# npm1300_qeaa_config4.net
KiCad netlist of a schematic drawn in Altium Designer
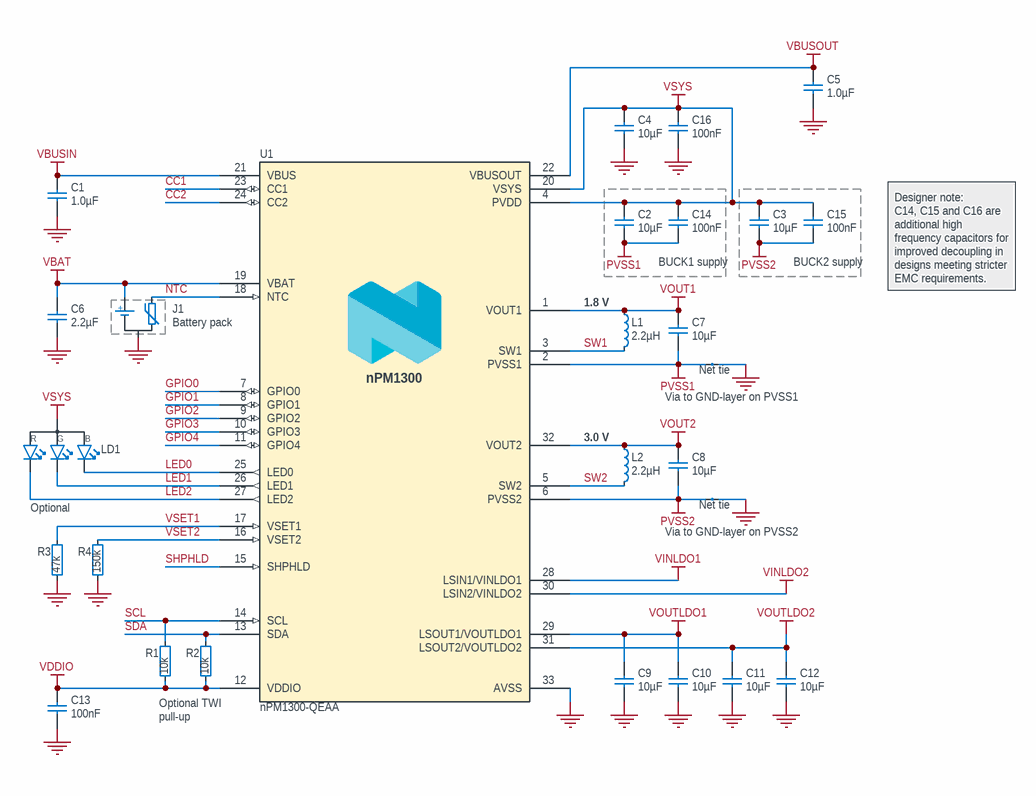
[diagram p0: npm1300_qeaa_config4.SchDoc]

(export (version "E")
  (design (tool "Eeschema 10.0.6"))
  (components
    (comp (ref "C1")
      (value "1.0µF")
      (footprint "CAPC1608X06L")
      (description "Capacitor, Ceramic, 1.0µF 10V X5R 0603,±10%")
      (fields
        (field (name "PART NUMBER") "C0603-1µ0-10V-X5R")
        (field (name "MANUFACTURER") "N.A.")
        (field (name "AUTHOR") "getr")
      )
      (libsource (lib "AltiumLib") (part "CAP"))
    )
    (comp (ref "C2")
      (value "10µF")
      (footprint "CAPC1608X06L")
      (description "Capacitor, X5R, ±20%")
      (fields
        (field (name "PART NUMBER") "C0603-10µ")
        (field (name "MANUFACTURER") "N.A.")
        (field (name "AUTHOR") "rsk")
      )
      (libsource (lib "AltiumLib") (part "CAP"))
    )
    (comp (ref "C3")
      (value "10µF")
      (footprint "CAPC1608X06L")
      (description "Capacitor, X5R, ±20%")
      (fields
        (field (name "PART NUMBER") "C0603-10µ")
        (field (name "MANUFACTURER") "N.A.")
        (field (name "AUTHOR") "rsk")
      )
      (libsource (lib "AltiumLib") (part "CAP"))
    )
    (comp (ref "C4")
      (value "10µF")
      (footprint "CAPC1608X06L")
      (description "Capacitor, X5R, ±20%")
      (fields
        (field (name "PART NUMBER") "C0603-10µ")
        (field (name "MANUFACTURER") "N.A.")
        (field (name "AUTHOR") "rsk")
      )
      (libsource (lib "AltiumLib") (part "CAP"))
    )
    (comp (ref "C5")
      (value "1.0µF")
      (footprint "CAPC1608X06L")
      (description "Capacitor, Ceramic, 1.0µF 10V X5R 0603,±10%")
      (fields
        (field (name "PART NUMBER") "C0603-1µ0-10V-X5R")
        (field (name "MANUFACTURER") "N.A.")
        (field (name "AUTHOR") "getr")
      )
      (libsource (lib "AltiumLib") (part "CAP"))
    )
    (comp (ref "C6")
      (value "2.2µF")
      (footprint "CAPC1608X06L")
      (description "Capacitor, Ceramic, X7R, ±10%, 16V")
      (fields
        (field (name "PART NUMBER") "C0603-2.2µ-16V-X7R")
        (field (name "MANUFACTURER") "Taiyo Yuden")
        (field (name "AUTHOR") "rsk")
      )
      (libsource (lib "AltiumLib") (part "CAP"))
    )
    (comp (ref "C7")
      (value "10µF")
      (footprint "CAPC1608X06L")
      (description "Capacitor, X5R, ±20%")
      (fields
        (field (name "PART NUMBER") "C0603-10µ")
        (field (name "MANUFACTURER") "N.A.")
        (field (name "AUTHOR") "rsk")
      )
      (libsource (lib "AltiumLib") (part "CAP"))
    )
    (comp (ref "C8")
      (value "10µF")
      (footprint "CAPC1608X06L")
      (description "Capacitor, X5R, ±20%")
      (fields
        (field (name "PART NUMBER") "C0603-10µ")
        (field (name "MANUFACTURER") "N.A.")
        (field (name "AUTHOR") "rsk")
      )
      (libsource (lib "AltiumLib") (part "CAP"))
    )
    (comp (ref "C9")
      (value "10µF")
      (footprint "CAPC1608X06L")
      (description "Capacitor, X5R, ±20%")
      (fields
        (field (name "PART NUMBER") "C0603-10µ")
        (field (name "MANUFACTURER") "N.A.")
        (field (name "AUTHOR") "rsk")
      )
      (libsource (lib "AltiumLib") (part "CAP"))
    )
    (comp (ref "C10")
      (value "10µF")
      (footprint "CAPC1608X06L")
      (description "Capacitor, X5R, ±20%")
      (fields
        (field (name "PART NUMBER") "C0603-10µ")
        (field (name "MANUFACTURER") "N.A.")
        (field (name "AUTHOR") "rsk")
      )
      (libsource (lib "AltiumLib") (part "CAP"))
    )
    (comp (ref "C11")
      (value "10µF")
      (footprint "CAPC1608X06L")
      (description "Capacitor, X5R, ±20%")
      (fields
        (field (name "PART NUMBER") "C0603-10µ")
        (field (name "MANUFACTURER") "N.A.")
        (field (name "AUTHOR") "rsk")
      )
      (libsource (lib "AltiumLib") (part "CAP"))
    )
    (comp (ref "C12")
      (value "10µF")
      (footprint "CAPC1608X06L")
      (description "Capacitor, X5R, ±20%")
      (fields
        (field (name "PART NUMBER") "C0603-10µ")
        (field (name "MANUFACTURER") "N.A.")
        (field (name "AUTHOR") "rsk")
      )
      (libsource (lib "AltiumLib") (part "CAP"))
    )
    (comp (ref "C13")
      (value "100nF")
      (footprint "CAPC0603X03L_C")
      (description "Capacitor, X5R, ±10%, 100nF, 16V")
      (fields
        (field (name "PART NUMBER") "C0201-100n")
        (field (name "MANUFACTURER") "N.A.")
        (field (name "AUTHOR") "rsk")
      )
      (libsource (lib "AltiumLib") (part "CAP"))
    )
    (comp (ref "C14")
      (value "100nF")
      (footprint "CAPC1005X04L")
      (description "Capacitor, Ceramic, X7R, ±20%, 16V")
      (fields
        (field (name "PART NUMBER") "C0402-100n-16V-X7R-C0402C104M4RAC7867")
        (field (name "MANUFACTURER") "Kemet")
        (field (name "AUTHOR") "getr")
      )
      (libsource (lib "AltiumLib") (part "CAP"))
    )
    (comp (ref "C15")
      (value "100nF")
      (footprint "CAPC1005X04L")
      (description "Capacitor, Ceramic, X7R, ±20%, 16V")
      (fields
        (field (name "PART NUMBER") "C0402-100n-16V-X7R-C0402C104M4RAC7867")
        (field (name "MANUFACTURER") "Kemet")
        (field (name "AUTHOR") "getr")
      )
      (libsource (lib "AltiumLib") (part "CAP"))
    )
    (comp (ref "C16")
      (value "100nF")
      (footprint "CAPC1005X04L")
      (description "Capacitor, Ceramic, X7R, ±20%, 16V")
      (fields
        (field (name "PART NUMBER") "C0402-100n-16V-X7R-C0402C104M4RAC7867")
        (field (name "MANUFACTURER") "Kemet")
        (field (name "AUTHOR") "getr")
      )
      (libsource (lib "AltiumLib") (part "CAP"))
    )
    (comp (ref "J1")
      (value "Battery pack")
      (footprint "TP_3x1mm_TH")
      (description "Battery pack with NTC")
      (fields
        (field (name "PART NUMBER") "Battery_w/NTC_TP")
        (field (name "MANUFACTURER") "N.A.")
        (field (name "AUTHOR") "rsk")
      )
      (libsource (lib "AltiumLib") (part "Battery_pack_NTC"))
    )
    (comp (ref "L1")
      (value "2.2µH")
      (footprint "INDC2016X10N")
      (description "Inductor, Irms=2.5A, Isat=2.9A, ±20%, DCR=73mΩ")
      (fields
        (field (name "PART NUMBER") "L0806-2µ2-2500mA-73mOhm-CIGT201610EH2R2MNE")
        (field (name "MANUFACTURER") "Samsung Electro-Mechanics America")
        (field (name "AUTHOR") "rsk")
      )
      (libsource (lib "AltiumLib") (part "IND"))
    )
    (comp (ref "L2")
      (value "2.2µH")
      (footprint "INDC2016X10N")
      (description "Inductor, Irms=2.5A, Isat=2.9A, ±20%, DCR=73mΩ")
      (fields
        (field (name "PART NUMBER") "L0806-2µ2-2500mA-73mOhm-CIGT201610EH2R2MNE")
        (field (name "MANUFACTURER") "Samsung Electro-Mechanics America")
        (field (name "AUTHOR") "rsk")
      )
      (libsource (lib "AltiumLib") (part "IND"))
    )
    (comp (ref "LD1")
      (value "LED RGB")
      (footprint "LED_RGB_0603")
      (description "RGB LED 1.60 mm x 0.80 mm SMD")
      (fields
        (field (name "PART NUMBER") "APHF1608LSEEQBDZGKC")
        (field (name "MANUFACTURER") "Kingbright Company LLC")
        (field (name "AUTHOR") "rsk")
      )
      (libsource (lib "AltiumLib") (part "D{colon}LED_RGB"))
    )
    (comp (ref "NT1")
      (value "Net tie")
      (footprint "2 PIN STARPOINT")
      (description "Starpoint")
      (fields
        (field (name "PART NUMBER") "2 pin starpoint")
        (field (name "MANUFACTURER") "N.A.")
        (field (name "AUTHOR") "rsk")
      )
      (libsource (lib "AltiumLib") (part "2 pin starpoint"))
    )
    (comp (ref "NT2")
      (value "Net tie")
      (footprint "2 PIN STARPOINT")
      (description "Starpoint")
      (fields
        (field (name "PART NUMBER") "2 pin starpoint")
        (field (name "MANUFACTURER") "N.A.")
        (field (name "AUTHOR") "rsk")
      )
      (libsource (lib "AltiumLib") (part "2 pin starpoint"))
    )
    (comp (ref "R1")
      (value "10k")
      (footprint "RESC0603X03L_C")
      (description "Resistor, ±1%, 0.05W")
      (fields
        (field (name "PART NUMBER") "R0201-10k")
        (field (name "MANUFACTURER") "N.A.")
        (field (name "AUTHOR") "rsk")
      )
      (libsource (lib "AltiumLib") (part "RES"))
    )
    (comp (ref "R2")
      (value "10k")
      (footprint "RESC0603X03L_C")
      (description "Resistor, ±1%, 0.05W")
      (fields
        (field (name "PART NUMBER") "R0201-10k")
        (field (name "MANUFACTURER") "N.A.")
        (field (name "AUTHOR") "rsk")
      )
      (libsource (lib "AltiumLib") (part "RES"))
    )
    (comp (ref "R3")
      (value "47k")
      (footprint "RESC0603X03L_C")
      (description "Resistor, ±1%, 0.05W")
      (fields
        (field (name "PART NUMBER") "R0201-47k")
        (field (name "MANUFACTURER") "N.A.")
        (field (name "AUTHOR") "rsk")
      )
      (libsource (lib "AltiumLib") (part "RES"))
    )
    (comp (ref "R4")
      (value "150k")
      (footprint "RESC0603X03L_C")
      (description "Resistor, ±1%, 0.05W")
      (fields
        (field (name "PART NUMBER") "R0201-150k")
        (field (name "MANUFACTURER") "N.A.")
        (field (name "AUTHOR") "rsk")
      )
      (libsource (lib "AltiumLib") (part "RES"))
    )
    (comp (ref "U1")
      (value "nPM1300-QEAA")
      (footprint "Nordic_QFN50P500X500X90-33N")
      (fields (field (name "MANUFACTURER") "Nordic Semiconductor") (field (name "AUTHOR") "eisk"))
      (libsource (lib "AltiumLib") (part "nPM1300_QEAA"))
    )
  )
  (nets
    (net (code "1") (name "/CC1") (class "Default")
      (node (ref "U1") (pin "23") (pinfunction "CC1_23") (pintype "bidirectional"))
    )
    (net (code "2") (name "/CC2") (class "Default")
      (node (ref "U1") (pin "24") (pinfunction "CC2_24") (pintype "bidirectional"))
    )
    (net (code "3") (name "/GPIO0") (class "Default")
      (node (ref "U1") (pin "7") (pinfunction "GPIO0_7") (pintype "bidirectional"))
    )
    (net (code "4") (name "/GPIO1") (class "Default")
      (node (ref "U1") (pin "8") (pinfunction "GPIO1_8") (pintype "bidirectional"))
    )
    (net (code "5") (name "/GPIO2") (class "Default")
      (node (ref "U1") (pin "9") (pinfunction "GPIO2_9") (pintype "bidirectional"))
    )
    (net (code "6") (name "/GPIO3") (class "Default")
      (node (ref "U1") (pin "10") (pinfunction "GPIO3_10") (pintype "bidirectional"))
    )
    (net (code "7") (name "/GPIO4") (class "Default")
      (node (ref "U1") (pin "11") (pinfunction "GPIO4_11") (pintype "bidirectional"))
    )
    (net (code "8") (name "/LED0") (class "Default")
      (node (ref "LD1") (pin "3") (pinfunction "C_BLUE_3") (pintype "passive"))
      (node (ref "U1") (pin "25") (pinfunction "LED0_25") (pintype "output"))
    )
    (net (code "9") (name "/LED1") (class "Default")
      (node (ref "LD1") (pin "2") (pinfunction "C_GREEN_2") (pintype "passive"))
      (node (ref "U1") (pin "26") (pinfunction "LED1_26") (pintype "output"))
    )
    (net (code "10") (name "/LED2") (class "Default")
      (node (ref "LD1") (pin "1") (pinfunction "C_RED_1") (pintype "passive"))
      (node (ref "U1") (pin "27") (pinfunction "LED2_27") (pintype "output"))
    )
    (net (code "11") (name "/NTC") (class "Default")
      (node (ref "J1") (pin "2") (pinfunction "NTC_2") (pintype "passive"))
      (node (ref "U1") (pin "18") (pinfunction "NTC_18") (pintype "input"))
    )
    (net (code "12") (name "/SCL") (class "Default")
      (node (ref "R1") (pin "1") (pinfunction "1_1") (pintype "passive"))
      (node (ref "U1") (pin "14") (pinfunction "SCL_14") (pintype "input"))
    )
    (net (code "13") (name "/SDA") (class "Default")
      (node (ref "R2") (pin "1") (pinfunction "1_1") (pintype "passive"))
      (node (ref "U1") (pin "13") (pinfunction "SDA_13") (pintype "open_collector"))
    )
    (net (code "14") (name "/SHPHLD") (class "Default")
      (node (ref "U1") (pin "15") (pinfunction "SHPHLD_15") (pintype "input"))
    )
    (net (code "15") (name "/SW1") (class "Default")
      (node (ref "L1") (pin "2") (pinfunction "2_2") (pintype "passive"))
      (node (ref "U1") (pin "3") (pinfunction "SW1_3") (pintype "power_in"))
    )
    (net (code "16") (name "/SW2") (class "Default")
      (node (ref "L2") (pin "2") (pinfunction "2_2") (pintype "passive"))
      (node (ref "U1") (pin "5") (pinfunction "SW2_5") (pintype "power_in"))
    )
    (net (code "17") (name "/VSET1") (class "Default")
      (node (ref "R3") (pin "1") (pinfunction "1_1") (pintype "passive"))
      (node (ref "U1") (pin "17") (pinfunction "VSET1_17") (pintype "input"))
    )
    (net (code "18") (name "/VSET2") (class "Default")
      (node (ref "R4") (pin "1") (pinfunction "1_1") (pintype "passive"))
      (node (ref "U1") (pin "16") (pinfunction "VSET2_16") (pintype "input"))
    )
    (net (code "19") (name "GND") (class "Default")
      (node (ref "C1") (pin "1") (pinfunction "1_1") (pintype "passive"))
      (node (ref "C10") (pin "1") (pinfunction "1_1") (pintype "passive"))
      (node (ref "C11") (pin "1") (pinfunction "1_1") (pintype "passive"))
      (node (ref "C12") (pin "1") (pinfunction "1_1") (pintype "passive"))
      (node (ref "C13") (pin "2") (pinfunction "2_2") (pintype "passive"))
      (node (ref "C16") (pin "2") (pinfunction "2_2") (pintype "passive"))
      (node (ref "C4") (pin "1") (pinfunction "1_1") (pintype "passive"))
      (node (ref "C5") (pin "1") (pinfunction "1_1") (pintype "passive"))
      (node (ref "C6") (pin "1") (pinfunction "1_1") (pintype "passive"))
      (node (ref "C9") (pin "1") (pinfunction "1_1") (pintype "passive"))
      (node (ref "J1") (pin "1") (pinfunction "GND_1") (pintype "passive"))
      (node (ref "NT1") (pin "1") (pintype "passive"))
      (node (ref "NT2") (pin "1") (pintype "passive"))
      (node (ref "R3") (pin "2") (pinfunction "2_2") (pintype "passive"))
      (node (ref "R4") (pin "2") (pinfunction "2_2") (pintype "passive"))
      (node (ref "U1") (pin "33") (pinfunction "AVSS_33") (pintype "power_in"))
    )
    (net (code "20") (name "PVSS1") (class "Default")
      (node (ref "C14") (pin "2") (pinfunction "2_2") (pintype "passive"))
      (node (ref "C2") (pin "1") (pinfunction "1_1") (pintype "passive"))
      (node (ref "C7") (pin "1") (pinfunction "1_1") (pintype "passive"))
      (node (ref "NT1") (pin "2") (pintype "passive"))
      (node (ref "U1") (pin "2") (pinfunction "PVSS1_2") (pintype "power_in"))
    )
    (net (code "21") (name "PVSS2") (class "Default")
      (node (ref "C15") (pin "2") (pinfunction "2_2") (pintype "passive"))
      (node (ref "C3") (pin "1") (pinfunction "1_1") (pintype "passive"))
      (node (ref "C8") (pin "1") (pinfunction "1_1") (pintype "passive"))
      (node (ref "NT2") (pin "2") (pintype "passive"))
      (node (ref "U1") (pin "6") (pinfunction "PVSS2_6") (pintype "power_in"))
    )
    (net (code "22") (name "VBAT") (class "Default")
      (node (ref "C6") (pin "2") (pinfunction "2_2") (pintype "passive"))
      (node (ref "J1") (pin "3") (pinfunction "V+_3") (pintype "passive"))
      (node (ref "U1") (pin "19") (pinfunction "VBAT_19") (pintype "passive"))
    )
    (net (code "23") (name "VBUSIN") (class "Default")
      (node (ref "C1") (pin "2") (pinfunction "2_2") (pintype "passive"))
      (node (ref "U1") (pin "21") (pinfunction "VBUS_21") (pintype "power_in"))
    )
    (net (code "24") (name "VBUSOUT") (class "Default")
      (node (ref "C5") (pin "2") (pinfunction "2_2") (pintype "passive"))
      (node (ref "U1") (pin "22") (pinfunction "VBUSOUT_22") (pintype "power_in"))
    )
    (net (code "25") (name "VDDIO") (class "Default")
      (node (ref "C13") (pin "1") (pinfunction "1_1") (pintype "passive"))
      (node (ref "R1") (pin "2") (pinfunction "2_2") (pintype "passive"))
      (node (ref "R2") (pin "2") (pinfunction "2_2") (pintype "passive"))
      (node (ref "U1") (pin "12") (pinfunction "VDDIO_12") (pintype "power_in"))
    )
    (net (code "26") (name "VINLDO1") (class "Default")
      (node (ref "U1") (pin "28") (pinfunction "LSIN1/VINLDO1_28") (pintype "power_in"))
    )
    (net (code "27") (name "VINLDO2") (class "Default")
      (node (ref "U1") (pin "30") (pinfunction "LSIN2/VINLDO2_30") (pintype "power_in"))
    )
    (net (code "28") (name "VOUT1") (class "Default")
      (node (ref "C7") (pin "2") (pinfunction "2_2") (pintype "passive"))
      (node (ref "L1") (pin "1") (pinfunction "1_1") (pintype "passive"))
      (node (ref "U1") (pin "1") (pinfunction "VOUT1_1") (pintype "power_in"))
    )
    (net (code "29") (name "VOUT2") (class "Default")
      (node (ref "C8") (pin "2") (pinfunction "2_2") (pintype "passive"))
      (node (ref "L2") (pin "1") (pinfunction "1_1") (pintype "passive"))
      (node (ref "U1") (pin "32") (pinfunction "VOUT2_32") (pintype "power_in"))
    )
    (net (code "30") (name "VOUTLDO1") (class "Default")
      (node (ref "C10") (pin "2") (pinfunction "2_2") (pintype "passive"))
      (node (ref "C9") (pin "2") (pinfunction "2_2") (pintype "passive"))
      (node (ref "U1") (pin "29") (pinfunction "LSOUT1/VOUTLDO1_29") (pintype "power_in"))
    )
    (net (code "31") (name "VOUTLDO2") (class "Default")
      (node (ref "C11") (pin "2") (pinfunction "2_2") (pintype "passive"))
      (node (ref "C12") (pin "2") (pinfunction "2_2") (pintype "passive"))
      (node (ref "U1") (pin "31") (pinfunction "LSOUT2/VOUTLDO2_31") (pintype "power_in"))
    )
    (net (code "32") (name "VSYS") (class "Default")
      (node (ref "C14") (pin "1") (pinfunction "1_1") (pintype "passive"))
      (node (ref "C15") (pin "1") (pinfunction "1_1") (pintype "passive"))
      (node (ref "C16") (pin "1") (pinfunction "1_1") (pintype "passive"))
      (node (ref "C2") (pin "2") (pinfunction "2_2") (pintype "passive"))
      (node (ref "C3") (pin "2") (pinfunction "2_2") (pintype "passive"))
      (node (ref "C4") (pin "2") (pinfunction "2_2") (pintype "passive"))
      (node (ref "LD1") (pin "4") (pinfunction "A_4") (pintype "passive"))
      (node (ref "U1") (pin "20") (pinfunction "VSYS_20") (pintype "power_in"))
      (node (ref "U1") (pin "4") (pinfunction "PVDD_4") (pintype "power_in"))
    )
  )
)
